# hx1.net
KiCad netlist of a schematic drawn in EAGLE
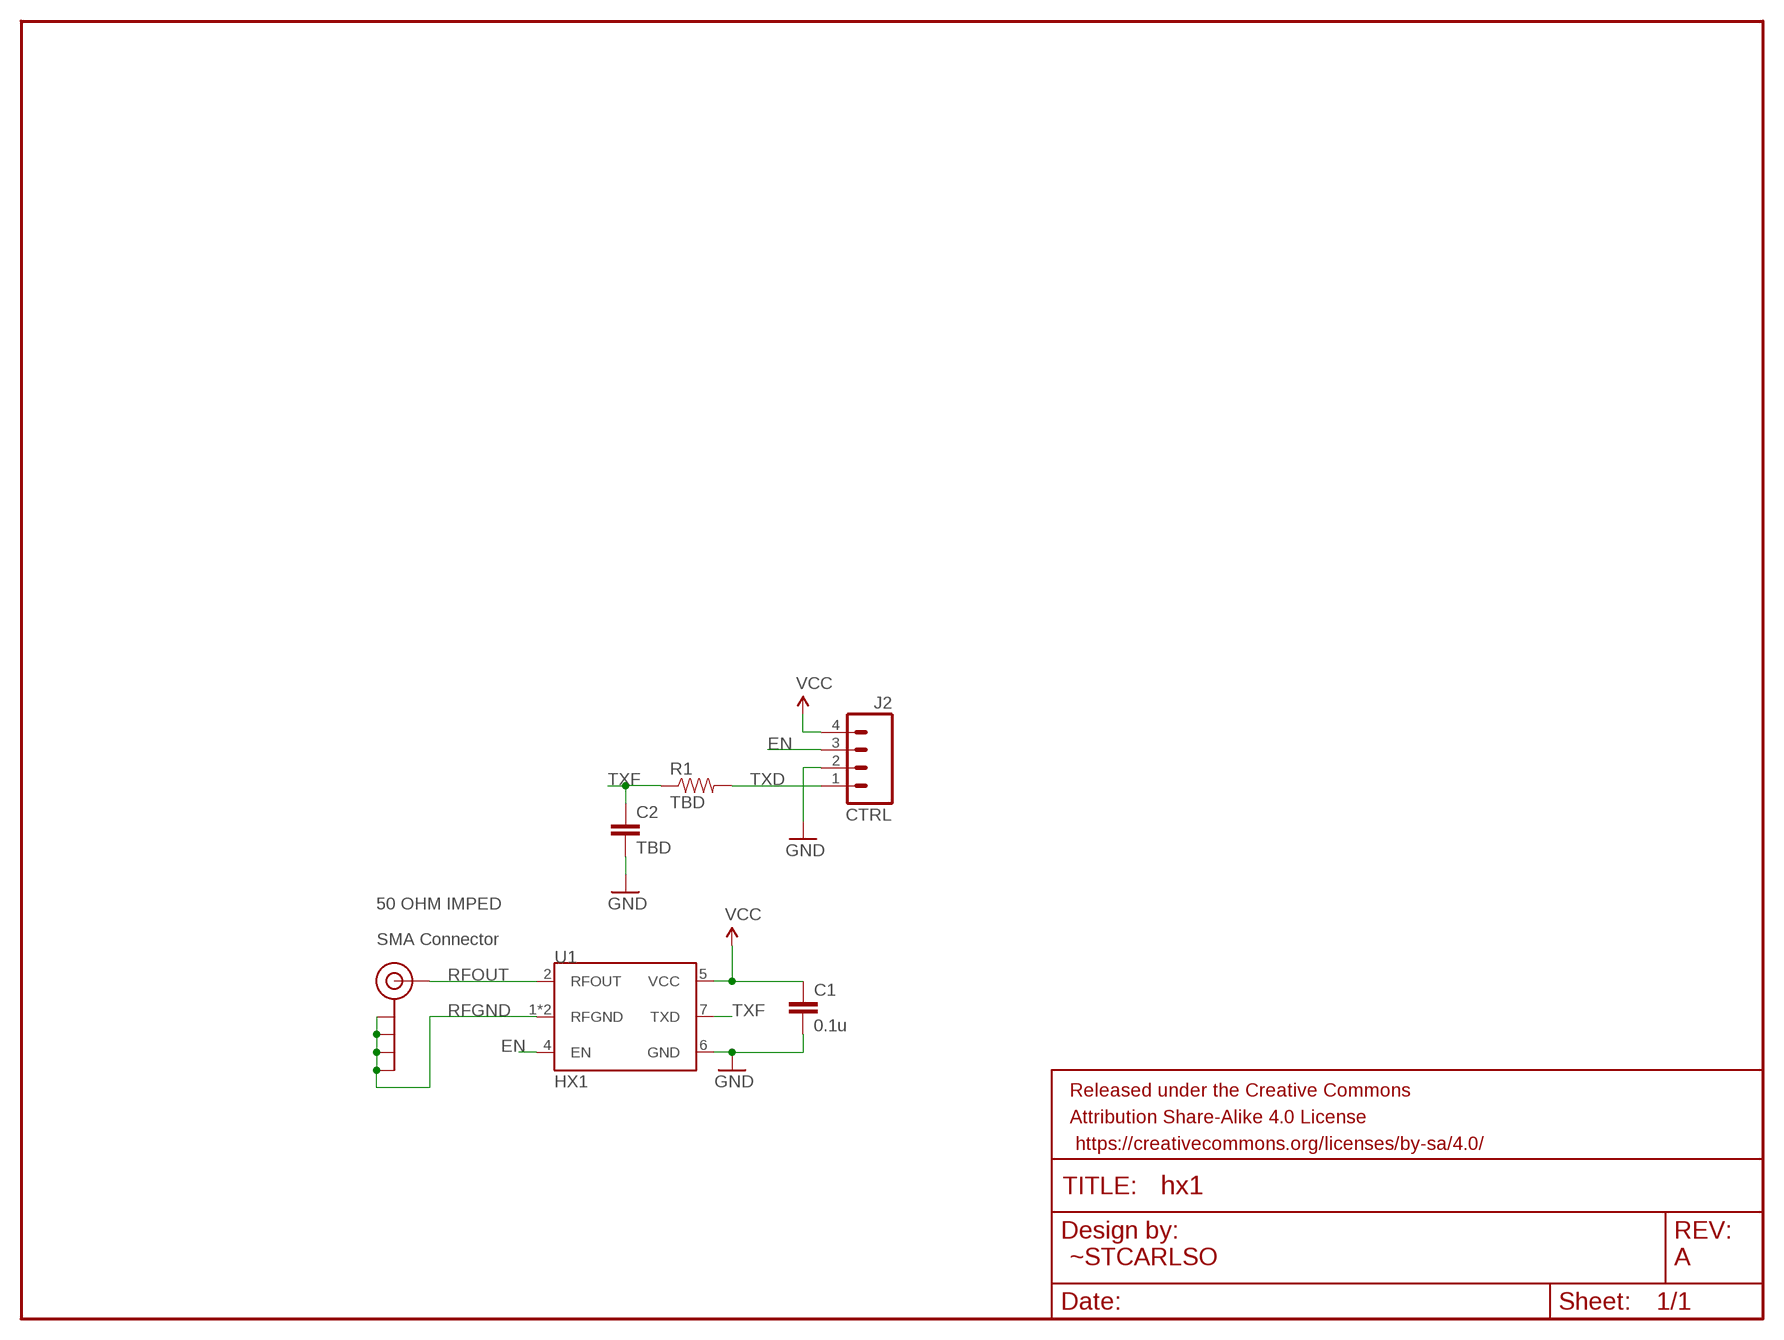
[diagram p0: schematic, sheet 1]

(export (version "E")
  (design (tool "Eeschema 10.0.6"))
  (components
    (comp (ref "C1")
      (value "0.1u")
      (footprint "eagle-import:CAP-PTH-SMALL")
      (libsource (lib "eagle-import") (part "CAPPTH"))
    )
    (comp (ref "C2")
      (value "TBD")
      (footprint "eagle-import:CAP-PTH-SMALL")
      (libsource (lib "eagle-import") (part "CAPPTH"))
    )
    (comp (ref "FRAME1")
      (value "FRAME-LETTERNO_PACKAGE")
      (footprint "eagle-import:DUMMY")
      (fields (field (name "DESIGNER") "Nobody"))
      (libsource (lib "eagle-import") (part "FRAME-LETTERNO_PACKAGE"))
    )
    (comp (ref "J1")
      (value "SMA_EDGE")
      (footprint "eagle-import:SMA-EDGE")
      (libsource (lib "eagle-import") (part "SMA_EDGE"))
    )
    (comp (ref "J2")
      (value "CTRL")
      (footprint "eagle-import:1X04")
      (libsource (lib "eagle-import") (part "M04PTH"))
    )
    (comp (ref "R1")
      (value "TBD")
      (footprint "eagle-import:AXIAL-0.3")
      (libsource (lib "eagle-import") (part "RESISTORAXIAL-0.3"))
    )
    (comp (ref "U1")
      (value "HX1")
      (footprint "eagle-import:1X12")
      (libsource (lib "eagle-import") (part "HX1"))
    )
  )
  (nets
    (net (code "1") (name "/EN") (class "Default")
      (node (ref "J2") (pin "3") (pinfunction "3_3") (pintype "passive"))
      (node (ref "U1") (pin "4") (pinfunction "EN_4") (pintype "input"))
    )
    (net (code "2") (name "/RFGND") (class "Default")
      (node (ref "J1") (pin "GND@0") (pinfunction "GND_GND@0") (pintype "bidirectional"))
      (node (ref "J1") (pin "GND@1") (pinfunction "GND_GND@1") (pintype "bidirectional"))
      (node (ref "J1") (pin "GND@2") (pinfunction "GND_GND@2") (pintype "bidirectional"))
      (node (ref "J1") (pin "GND@3") (pinfunction "GND_GND@3") (pintype "bidirectional"))
      (node (ref "U1") (pin "1") (pinfunction "RFGND_1") (pintype "power_in"))
      (node (ref "U1") (pin "3") (pinfunction "RFGND_3") (pintype "power_in"))
    )
    (net (code "3") (name "/RFOUT") (class "Default")
      (node (ref "J1") (pin "SIG") (pinfunction "SIGNAL_SIG") (pintype "bidirectional"))
      (node (ref "U1") (pin "2") (pinfunction "RFOUT_2") (pintype "output"))
    )
    (net (code "4") (name "/TXD") (class "Default")
      (node (ref "J2") (pin "1") (pinfunction "1_1") (pintype "passive"))
      (node (ref "R1") (pin "P$2") (pinfunction "2_P$2") (pintype "passive"))
    )
    (net (code "5") (name "/TXF") (class "Default")
      (node (ref "C2") (pin "1") (pinfunction "1_1") (pintype "passive"))
      (node (ref "R1") (pin "P$1") (pinfunction "1_P$1") (pintype "passive"))
      (node (ref "U1") (pin "7") (pinfunction "TXD_7") (pintype "input"))
    )
    (net (code "6") (name "GND") (class "Default")
      (node (ref "C1") (pin "2") (pinfunction "2_2") (pintype "passive"))
      (node (ref "C2") (pin "2") (pinfunction "2_2") (pintype "passive"))
      (node (ref "J2") (pin "2") (pinfunction "2_2") (pintype "passive"))
      (node (ref "U1") (pin "6") (pinfunction "GND_6") (pintype "power_in"))
    )
    (net (code "7") (name "VCC") (class "Default")
      (node (ref "C1") (pin "1") (pinfunction "1_1") (pintype "passive"))
      (node (ref "J2") (pin "4") (pinfunction "4_4") (pintype "passive"))
      (node (ref "U1") (pin "5") (pinfunction "VCC_5") (pintype "power_in"))
    )
  )
)
